# paperclick_v1.net
KiCad netlist of a schematic drawn in EAGLE
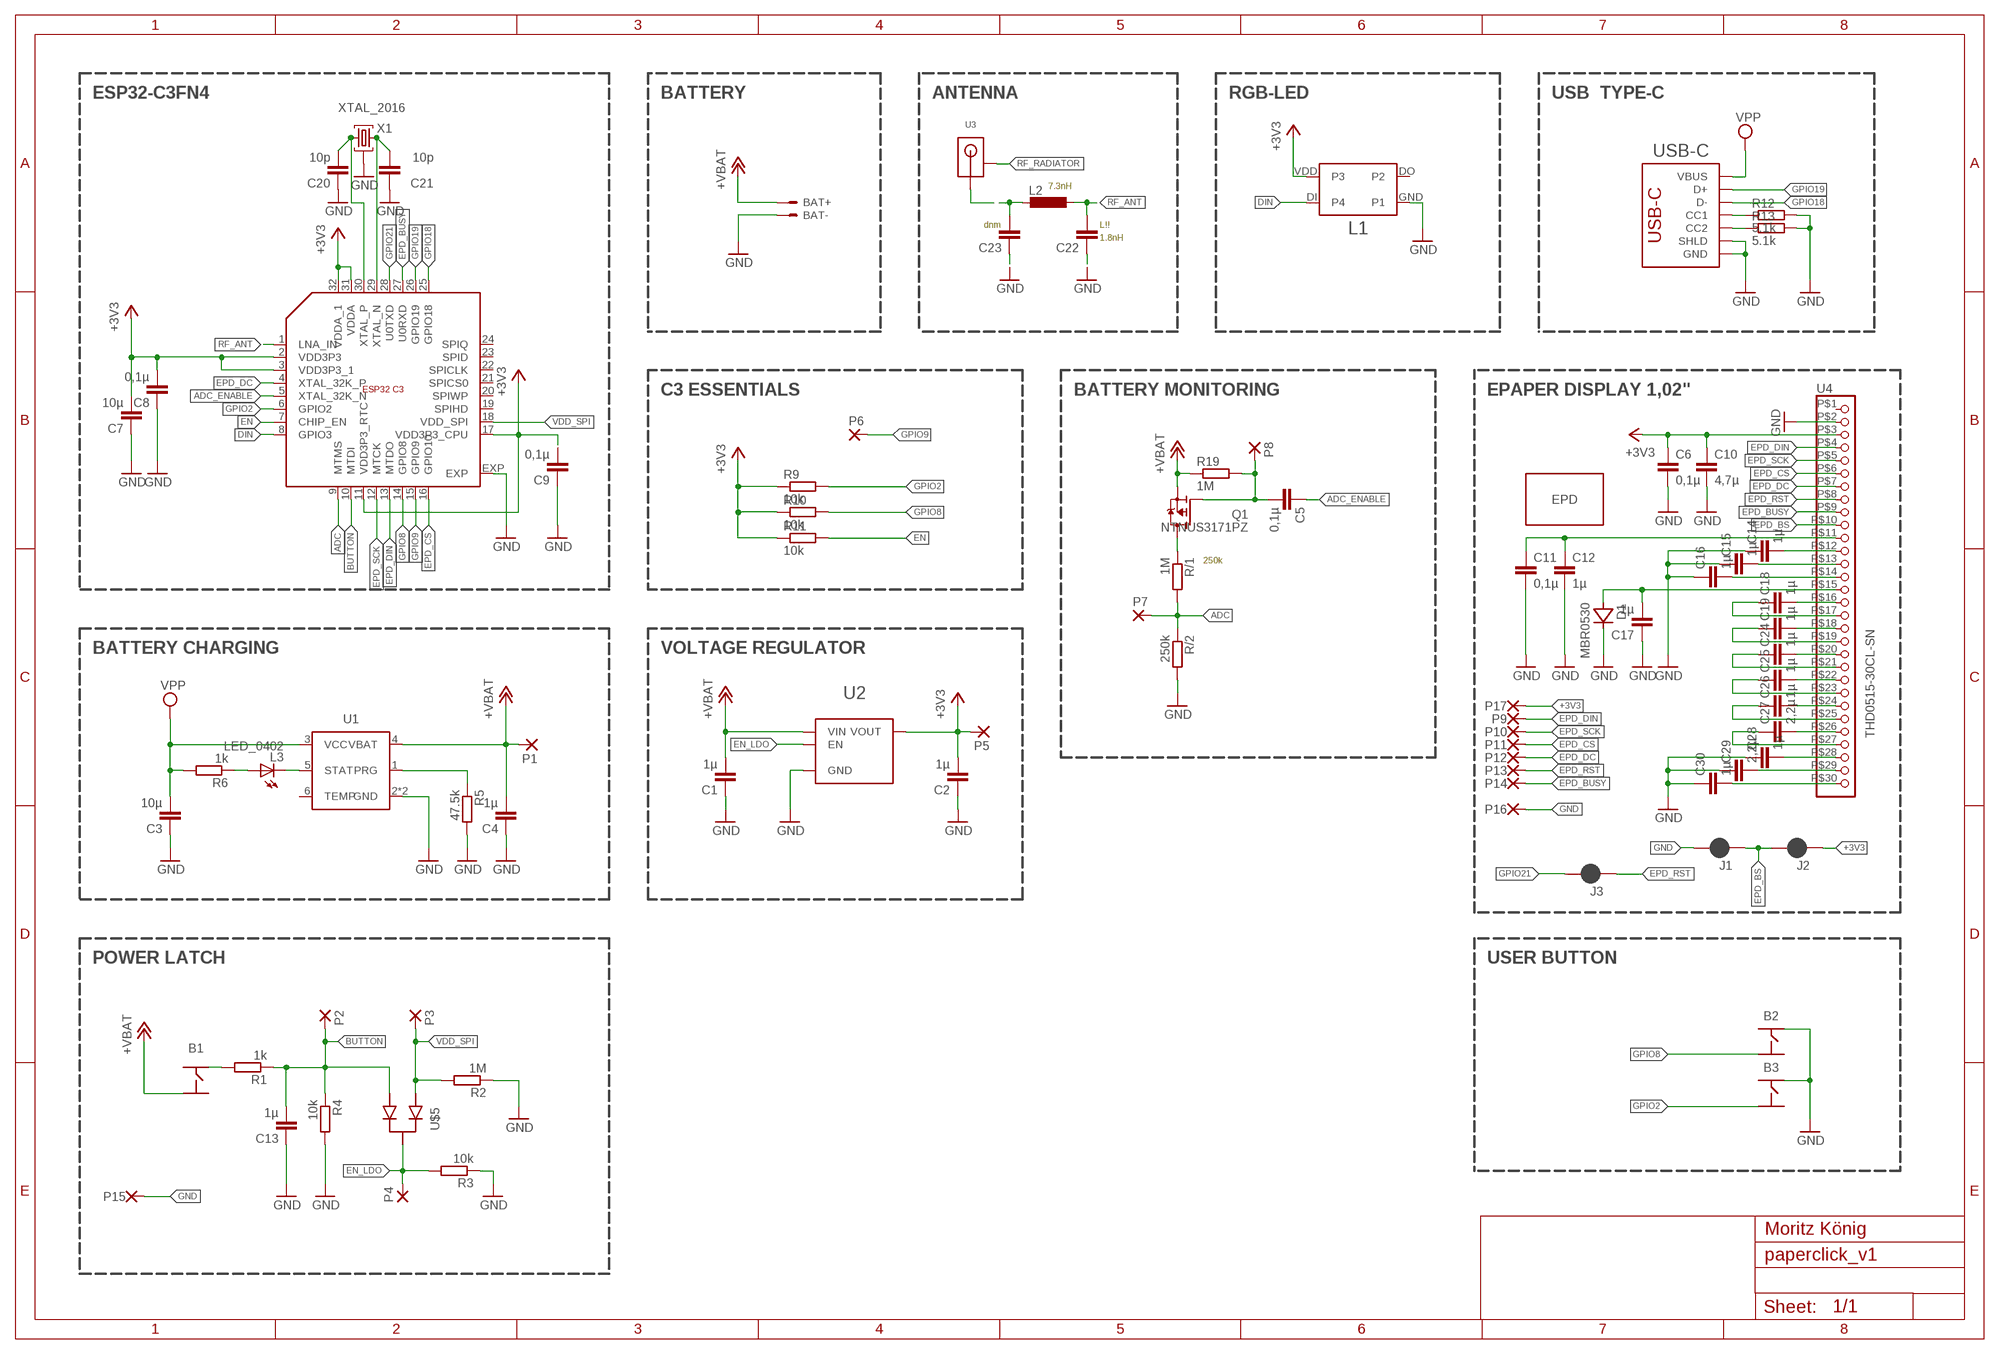
[diagram p0: schematic, sheet 1]

(export (version "E")
  (design (tool "Eeschema 10.0.6"))
  (components
    (comp (ref "B1")
      (value "BUTTON_4PIN_TS-1070A")
      (footprint "eagle-import:BUTTON_WHITE_SMD")
      (libsource (lib "eagle-import") (part "BUTTON_4PIN_TS-1070A"))
    )
    (comp (ref "B2")
      (value "PTS840ESDGMSMTRLFS")
      (footprint "eagle-import:PTS840ESDGMSMTRLFS")
      (libsource (lib "eagle-import") (part "PTS840ESDGMSMTRLFS"))
    )
    (comp (ref "B3")
      (value "PTS840ESDGMSMTRLFS")
      (footprint "eagle-import:PTS840ESDGMSMTRLFS")
      (libsource (lib "eagle-import") (part "PTS840ESDGMSMTRLFS"))
    )
    (comp (ref "BAT+")
      (value "TP/SP-1.5X1.0")
      (footprint "eagle-import:SOLDERPAD_1.5X1.0")
      (libsource (lib "eagle-import") (part "TP/SP-1.5X1.0"))
    )
    (comp (ref "BAT-")
      (value "TP/SP-1.5X1.0")
      (footprint "eagle-import:SOLDERPAD_1.5X1.0")
      (libsource (lib "eagle-import") (part "TP/SP-1.5X1.0"))
    )
    (comp (ref "C1")
      (value "1µ")
      (footprint "eagle-import:C0402_S")
      (libsource (lib "eagle-import") (part "C0402_S"))
    )
    (comp (ref "C2")
      (value "1µ")
      (footprint "eagle-import:C0402_S")
      (libsource (lib "eagle-import") (part "C0402_S"))
    )
    (comp (ref "C3")
      (value "10µ")
      (footprint "eagle-import:C0402_S")
      (libsource (lib "eagle-import") (part "C0402_S"))
    )
    (comp (ref "C4")
      (value "1µ")
      (footprint "eagle-import:C0402_S")
      (libsource (lib "eagle-import") (part "C0402_S"))
    )
    (comp (ref "C5")
      (value "0,1µ")
      (footprint "eagle-import:C0402_S")
      (libsource (lib "eagle-import") (part "C0402_S"))
    )
    (comp (ref "C6")
      (value "0,1µ")
      (footprint "eagle-import:C0402_S")
      (libsource (lib "eagle-import") (part "C0402_S"))
    )
    (comp (ref "C7")
      (value "10µ")
      (footprint "eagle-import:C0402_S")
      (libsource (lib "eagle-import") (part "C0402_S"))
    )
    (comp (ref "C8")
      (value "0,1µ")
      (footprint "eagle-import:C0402_S")
      (libsource (lib "eagle-import") (part "C0402_S"))
    )
    (comp (ref "C9")
      (value "0,1µ")
      (footprint "eagle-import:C0402_S")
      (libsource (lib "eagle-import") (part "C0402_S"))
    )
    (comp (ref "C10")
      (value "4,7µ")
      (footprint "eagle-import:C0402_S")
      (libsource (lib "eagle-import") (part "C0402_S"))
    )
    (comp (ref "C11")
      (value "0,1µ")
      (footprint "eagle-import:C0402_S")
      (libsource (lib "eagle-import") (part "C0402_S"))
    )
    (comp (ref "C12")
      (value "1µ")
      (footprint "eagle-import:C0402_S")
      (libsource (lib "eagle-import") (part "C0402_S"))
    )
    (comp (ref "C13")
      (value "1µ")
      (footprint "eagle-import:C0402_S")
      (libsource (lib "eagle-import") (part "C0402_S"))
    )
    (comp (ref "C14")
      (value "1µ")
      (footprint "eagle-import:C0402_S")
      (libsource (lib "eagle-import") (part "C0402_S"))
    )
    (comp (ref "C15")
      (value "1µ")
      (footprint "eagle-import:C0402_S")
      (libsource (lib "eagle-import") (part "C0402_S"))
    )
    (comp (ref "C16")
      (value "1µ")
      (footprint "eagle-import:C0402_S")
      (libsource (lib "eagle-import") (part "C0402_S"))
    )
    (comp (ref "C17")
      (value "1µ")
      (footprint "eagle-import:C0402_S")
      (libsource (lib "eagle-import") (part "C0402_S"))
    )
    (comp (ref "C18")
      (value "1µ")
      (footprint "eagle-import:C0402_S")
      (libsource (lib "eagle-import") (part "C0402_S"))
    )
    (comp (ref "C19")
      (value "1µ")
      (footprint "eagle-import:C0402_S")
      (libsource (lib "eagle-import") (part "C0402_S"))
    )
    (comp (ref "C20")
      (value "10p")
      (footprint "eagle-import:C0402_S")
      (libsource (lib "eagle-import") (part "C0402_S"))
    )
    (comp (ref "C21")
      (value "10p")
      (footprint "eagle-import:C0402_S")
      (libsource (lib "eagle-import") (part "C0402_S"))
    )
    (comp (ref "C22")
      (value "C0201")
      (footprint "eagle-import:C0201")
      (libsource (lib "eagle-import") (part "C0201"))
    )
    (comp (ref "C23")
      (value "C0201")
      (footprint "eagle-import:C0201")
      (libsource (lib "eagle-import") (part "C0201"))
    )
    (comp (ref "C24")
      (value "1µ")
      (footprint "eagle-import:C0402_S")
      (libsource (lib "eagle-import") (part "C0402_S"))
    )
    (comp (ref "C25")
      (value "1µ")
      (footprint "eagle-import:C0402_S")
      (libsource (lib "eagle-import") (part "C0402_S"))
    )
    (comp (ref "C26")
      (value "1µ")
      (footprint "eagle-import:C0402_S")
      (libsource (lib "eagle-import") (part "C0402_S"))
    )
    (comp (ref "C27")
      (value "2,2µ")
      (footprint "eagle-import:C0402_S")
      (libsource (lib "eagle-import") (part "C0402_S"))
    )
    (comp (ref "C28")
      (value "1µ")
      (footprint "eagle-import:C0402_S")
      (libsource (lib "eagle-import") (part "C0402_S"))
    )
    (comp (ref "C29")
      (value "2,2µ")
      (footprint "eagle-import:C0402_S")
      (libsource (lib "eagle-import") (part "C0402_S"))
    )
    (comp (ref "C30")
      (value "1µ")
      (footprint "eagle-import:C0402_S")
      (libsource (lib "eagle-import") (part "C0402_S"))
    )
    (comp (ref "D1")
      (value "MBR0530")
      (footprint "eagle-import:SOD123")
      (libsource (lib "eagle-import") (part "MBR0520"))
    )
    (comp (ref "ESP1")
      (value "ESP32_C3_QFN32")
      (footprint "eagle-import:QFN32")
      (libsource (lib "eagle-import") (part "ESP32_C3_QFN32"))
    )
    (comp (ref "J1")
      (value "SMT_JUMPER_2_NC_PASTE")
      (footprint "eagle-import:JUMPER_SMALL")
      (libsource (lib "eagle-import") (part "SMT_JUMPER_2_NC_PASTE"))
    )
    (comp (ref "J2")
      (value "SMT_JUMPER_2_NC_PASTE")
      (footprint "eagle-import:JUMPER_SMALL")
      (libsource (lib "eagle-import") (part "SMT_JUMPER_2_NC_PASTE"))
    )
    (comp (ref "J3")
      (value "SMT_JUMPER_2_NC_PASTE")
      (footprint "eagle-import:JUMPER_SMALL")
      (libsource (lib "eagle-import") (part "SMT_JUMPER_2_NC_PASTE"))
    )
    (comp (ref "L1")
      (value "WS2812_2020")
      (footprint "eagle-import:WS2812_2020")
      (libsource (lib "eagle-import") (part "WS2812_2020"))
    )
    (comp (ref "L2")
      (value "L0201")
      (footprint "eagle-import:L0201")
      (libsource (lib "eagle-import") (part "L0201"))
    )
    (comp (ref "L3")
      (value "LED_0402")
      (footprint "eagle-import:CHIPLED_0402")
      (libsource (lib "eagle-import") (part "LED_0402"))
    )
    (comp (ref "P1")
      (value "SMD-R1")
      (footprint "eagle-import:SMD-R1")
      (libsource (lib "eagle-import") (part "SMD-R1"))
    )
    (comp (ref "P2")
      (value "SMD-R1")
      (footprint "eagle-import:SMD-R1")
      (libsource (lib "eagle-import") (part "SMD-R1"))
    )
    (comp (ref "P3")
      (value "SMD-R1")
      (footprint "eagle-import:SMD-R1")
      (libsource (lib "eagle-import") (part "SMD-R1"))
    )
    (comp (ref "P4")
      (value "SMD-R1")
      (footprint "eagle-import:SMD-R1")
      (libsource (lib "eagle-import") (part "SMD-R1"))
    )
    (comp (ref "P5")
      (value "SMD-R1")
      (footprint "eagle-import:SMD-R1")
      (libsource (lib "eagle-import") (part "SMD-R1"))
    )
    (comp (ref "P6")
      (value "SMD-R1")
      (footprint "eagle-import:SMD-R1")
      (libsource (lib "eagle-import") (part "SMD-R1"))
    )
    (comp (ref "P7")
      (value "SMD-R1")
      (footprint "eagle-import:SMD-R1")
      (libsource (lib "eagle-import") (part "SMD-R1"))
    )
    (comp (ref "P8")
      (value "SMD-R1")
      (footprint "eagle-import:SMD-R1")
      (libsource (lib "eagle-import") (part "SMD-R1"))
    )
    (comp (ref "P9")
      (value "SMD-R1")
      (footprint "eagle-import:SMD-R1")
      (libsource (lib "eagle-import") (part "SMD-R1"))
    )
    (comp (ref "P10")
      (value "SMD-R1")
      (footprint "eagle-import:SMD-R1")
      (libsource (lib "eagle-import") (part "SMD-R1"))
    )
    (comp (ref "P11")
      (value "SMD-R1")
      (footprint "eagle-import:SMD-R1")
      (libsource (lib "eagle-import") (part "SMD-R1"))
    )
    (comp (ref "P12")
      (value "SMD-R1")
      (footprint "eagle-import:SMD-R1")
      (libsource (lib "eagle-import") (part "SMD-R1"))
    )
    (comp (ref "P13")
      (value "SMD-R1")
      (footprint "eagle-import:SMD-R1")
      (libsource (lib "eagle-import") (part "SMD-R1"))
    )
    (comp (ref "P14")
      (value "SMD-R1")
      (footprint "eagle-import:SMD-R1")
      (libsource (lib "eagle-import") (part "SMD-R1"))
    )
    (comp (ref "P15")
      (value "SMD-R1")
      (footprint "eagle-import:SMD-R1")
      (libsource (lib "eagle-import") (part "SMD-R1"))
    )
    (comp (ref "P16")
      (value "SMD-R1")
      (footprint "eagle-import:SMD-R1")
      (libsource (lib "eagle-import") (part "SMD-R1"))
    )
    (comp (ref "P17")
      (value "SMD-R1")
      (footprint "eagle-import:SMD-R1")
      (libsource (lib "eagle-import") (part "SMD-R1"))
    )
    (comp (ref "Q1")
      (value "NTNUS3171PZ")
      (footprint "eagle-import:SOT1123")
      (libsource (lib "eagle-import") (part "NTNUS3171PZ"))
    )
    (comp (ref "R/1")
      (value "1M")
      (footprint "eagle-import:R0402")
      (libsource (lib "eagle-import") (part "R0402"))
    )
    (comp (ref "R/2")
      (value "250k")
      (footprint "eagle-import:R0402")
      (libsource (lib "eagle-import") (part "R0402"))
    )
    (comp (ref "R1")
      (value "1k")
      (footprint "eagle-import:R0402")
      (libsource (lib "eagle-import") (part "R0402"))
    )
    (comp (ref "R2")
      (value "1M")
      (footprint "eagle-import:R0402")
      (libsource (lib "eagle-import") (part "R0402"))
    )
    (comp (ref "R3")
      (value "10k")
      (footprint "eagle-import:R0402")
      (libsource (lib "eagle-import") (part "R0402"))
    )
    (comp (ref "R4")
      (value "10k")
      (footprint "eagle-import:R0402")
      (libsource (lib "eagle-import") (part "R0402"))
    )
    (comp (ref "R5")
      (value "47.5k")
      (footprint "eagle-import:R0402")
      (libsource (lib "eagle-import") (part "R0402"))
    )
    (comp (ref "R6")
      (value "1k")
      (footprint "eagle-import:R0402")
      (libsource (lib "eagle-import") (part "R0402"))
    )
    (comp (ref "R9")
      (value "10k")
      (footprint "eagle-import:R0402")
      (libsource (lib "eagle-import") (part "R0402"))
    )
    (comp (ref "R10")
      (value "10k")
      (footprint "eagle-import:R0402")
      (libsource (lib "eagle-import") (part "R0402"))
    )
    (comp (ref "R11")
      (value "10k")
      (footprint "eagle-import:R0402")
      (libsource (lib "eagle-import") (part "R0402"))
    )
    (comp (ref "R12")
      (value "5.1k")
      (footprint "eagle-import:R0402")
      (libsource (lib "eagle-import") (part "R0402"))
    )
    (comp (ref "R13")
      (value "5.1k")
      (footprint "eagle-import:R0402")
      (libsource (lib "eagle-import") (part "R0402"))
    )
    (comp (ref "R19")
      (value "1M")
      (footprint "eagle-import:R0402")
      (libsource (lib "eagle-import") (part "R0402"))
    )
    (comp (ref "U$2")
      (value "EPD-102-30PIN-TW")
      (footprint "eagle-import:EPD-102-30PIN-TW")
      (libsource (lib "eagle-import") (part "EPD-102-30PIN-TW"))
    )
    (comp (ref "U$5")
      (value "DAN222")
      (footprint "eagle-import:SOT523")
      (libsource (lib "eagle-import") (part "DAN222"))
    )
    (comp (ref "U1")
      (value "WS4518D")
      (footprint "eagle-import:DFN-6")
      (libsource (lib "eagle-import") (part "WS4518D"))
    )
    (comp (ref "U2")
      (value "MIC5504")
      (footprint "eagle-import:TDFN4")
      (libsource (lib "eagle-import") (part "MIC5504"))
    )
    (comp (ref "U3")
      (value "ANT016008LCS2442MA2")
      (footprint "eagle-import:ANT016008LCS2442MA2")
      (libsource (lib "eagle-import") (part "ANT016008LCS2442MA2"))
    )
    (comp (ref "U4")
      (value "THD0515-30CL-SN")
      (footprint "eagle-import:THD0515-30CL-SN")
      (libsource (lib "eagle-import") (part "THD0515-30CL-SN"))
    )
    (comp (ref "USB-C")
      (value "USB_C_C393939")
      (footprint "eagle-import:USBC_C393939")
      (libsource (lib "eagle-import") (part "USB_C_C393939"))
    )
    (comp (ref "X1")
      (value "XTAL_2016")
      (footprint "eagle-import:XTAL_2016")
      (libsource (lib "eagle-import") (part "XTAL_2016"))
    )
  )
  (nets
    (net (code "1") (name "+3V3") (class "Default")
      (node (ref "C10") (pin "P$1") (pinfunction "1_P$1") (pintype "passive"))
      (node (ref "C2") (pin "P$2") (pinfunction "2_P$2") (pintype "passive"))
      (node (ref "C6") (pin "P$1") (pinfunction "1_P$1") (pintype "passive"))
      (node (ref "C7") (pin "P$2") (pinfunction "2_P$2") (pintype "passive"))
      (node (ref "C8") (pin "P$2") (pinfunction "2_P$2") (pintype "passive"))
      (node (ref "C9") (pin "P$2") (pinfunction "2_P$2") (pintype "passive"))
      (node (ref "ESP1") (pin "11") (pinfunction "VDD3P3_RTC_11") (pintype "bidirectional"))
      (node (ref "ESP1") (pin "17") (pinfunction "VDD3P3_CPU_17") (pintype "bidirectional"))
      (node (ref "ESP1") (pin "2") (pinfunction "VDD3P3_2") (pintype "bidirectional"))
      (node (ref "ESP1") (pin "3") (pinfunction "VDD3P3_1_3") (pintype "bidirectional"))
      (node (ref "ESP1") (pin "31") (pinfunction "VDDA_31") (pintype "bidirectional"))
      (node (ref "ESP1") (pin "32") (pinfunction "VDDA_1_32") (pintype "bidirectional"))
      (node (ref "J2") (pin "P$1") (pinfunction "1_P$1") (pintype "passive"))
      (node (ref "L1") (pin "VDD") (pinfunction "P3_VDD") (pintype "bidirectional"))
      (node (ref "P17") (pin "P$1") (pinfunction "P_P$1") (pintype "passive"))
      (node (ref "P5") (pin "P$1") (pinfunction "P_P$1") (pintype "passive"))
      (node (ref "R10") (pin "1") (pinfunction "1_1") (pintype "passive"))
      (node (ref "R11") (pin "1") (pinfunction "1_1") (pintype "passive"))
      (node (ref "R9") (pin "1") (pinfunction "1_1") (pintype "passive"))
      (node (ref "U2") (pin "P1") (pinfunction "VOUT_P1") (pintype "bidirectional"))
      (node (ref "U4") (pin "P$3") (pinfunction "3_P$3") (pintype "passive"))
    )
    (net (code "2") (name "+VBAT") (class "Default")
      (node (ref "B1") (pin "P$2") (pinfunction "3_P$2") (pintype "bidirectional"))
      (node (ref "BAT+") (pin "1") (pinfunction "S_1") (pintype "passive"))
      (node (ref "C1") (pin "P$2") (pinfunction "2_P$2") (pintype "passive"))
      (node (ref "C4") (pin "P$2") (pinfunction "2_P$2") (pintype "passive"))
      (node (ref "P1") (pin "P$1") (pinfunction "P_P$1") (pintype "passive"))
      (node (ref "Q1") (pin "2") (pinfunction "S_2") (pintype "passive"))
      (node (ref "R19") (pin "1") (pinfunction "1_1") (pintype "passive"))
      (node (ref "U1") (pin "4") (pinfunction "VBAT_4") (pintype "bidirectional"))
      (node (ref "U2") (pin "P4") (pinfunction "VIN_P4") (pintype "bidirectional"))
    )
    (net (code "3") (name "ADC") (class "Default")
      (node (ref "ESP1") (pin "9") (pinfunction "MTMS_9") (pintype "bidirectional"))
      (node (ref "P7") (pin "P$1") (pinfunction "P_P$1") (pintype "passive"))
      (node (ref "R/1") (pin "2") (pinfunction "2_2") (pintype "passive"))
      (node (ref "R/2") (pin "1") (pinfunction "1_1") (pintype "passive"))
    )
    (net (code "4") (name "ADC_ENABLE") (class "Default")
      (node (ref "C5") (pin "P$1") (pinfunction "1_P$1") (pintype "passive"))
      (node (ref "ESP1") (pin "5") (pinfunction "XTAL_32K_N_5") (pintype "bidirectional"))
    )
    (net (code "5") (name "BUTTON") (class "Default")
      (node (ref "C13") (pin "P$2") (pinfunction "2_P$2") (pintype "passive"))
      (node (ref "ESP1") (pin "10") (pinfunction "MTDI_10") (pintype "bidirectional"))
      (node (ref "P2") (pin "P$1") (pinfunction "P_P$1") (pintype "passive"))
      (node (ref "R1") (pin "1") (pinfunction "1_1") (pintype "passive"))
      (node (ref "R4") (pin "1") (pinfunction "1_1") (pintype "passive"))
      (node (ref "U$5") (pin "2") (pinfunction "2_2") (pintype "bidirectional"))
    )
    (net (code "6") (name "DIN") (class "Default")
      (node (ref "ESP1") (pin "8") (pinfunction "GPIO3_8") (pintype "bidirectional"))
      (node (ref "L1") (pin "DI") (pinfunction "P4_DI") (pintype "bidirectional"))
    )
    (net (code "7") (name "EN") (class "Default")
      (node (ref "ESP1") (pin "7") (pinfunction "CHIP_EN_7") (pintype "bidirectional"))
      (node (ref "R11") (pin "2") (pinfunction "2_2") (pintype "passive"))
    )
    (net (code "8") (name "EN_LDO") (class "Default")
      (node (ref "P4") (pin "P$1") (pinfunction "P_P$1") (pintype "passive"))
      (node (ref "R3") (pin "2") (pinfunction "2_2") (pintype "passive"))
      (node (ref "U$5") (pin "3") (pinfunction "3_3") (pintype "bidirectional"))
      (node (ref "U2") (pin "P3") (pinfunction "EN_P3") (pintype "bidirectional"))
    )
    (net (code "9") (name "EPD_BS") (class "Default")
      (node (ref "J1") (pin "P$1") (pinfunction "1_P$1") (pintype "passive"))
      (node (ref "J2") (pin "P$2") (pinfunction "2_P$2") (pintype "passive"))
      (node (ref "U4") (pin "P$10") (pinfunction "10_P$10") (pintype "passive"))
    )
    (net (code "10") (name "EPD_BUSY") (class "Default")
      (node (ref "ESP1") (pin "27") (pinfunction "U0RXD_27") (pintype "bidirectional"))
      (node (ref "P14") (pin "P$1") (pinfunction "P_P$1") (pintype "passive"))
      (node (ref "U4") (pin "P$9") (pinfunction "9_P$9") (pintype "passive"))
    )
    (net (code "11") (name "EPD_CS") (class "Default")
      (node (ref "ESP1") (pin "16") (pinfunction "GPIO10_16") (pintype "bidirectional"))
      (node (ref "P11") (pin "P$1") (pinfunction "P_P$1") (pintype "passive"))
      (node (ref "U4") (pin "P$6") (pinfunction "6_P$6") (pintype "passive"))
    )
    (net (code "12") (name "EPD_DC") (class "Default")
      (node (ref "ESP1") (pin "4") (pinfunction "XTAL_32K_P_4") (pintype "bidirectional"))
      (node (ref "P12") (pin "P$1") (pinfunction "P_P$1") (pintype "passive"))
      (node (ref "U4") (pin "P$7") (pinfunction "7_P$7") (pintype "passive"))
    )
    (net (code "13") (name "EPD_DIN") (class "Default")
      (node (ref "ESP1") (pin "13") (pinfunction "MTDO_13") (pintype "bidirectional"))
      (node (ref "P9") (pin "P$1") (pinfunction "P_P$1") (pintype "passive"))
      (node (ref "U4") (pin "P$4") (pinfunction "4_P$4") (pintype "passive"))
    )
    (net (code "14") (name "EPD_RST") (class "Default")
      (node (ref "J3") (pin "P$1") (pinfunction "1_P$1") (pintype "passive"))
      (node (ref "P13") (pin "P$1") (pinfunction "P_P$1") (pintype "passive"))
      (node (ref "U4") (pin "P$8") (pinfunction "8_P$8") (pintype "passive"))
    )
    (net (code "15") (name "EPD_SCK") (class "Default")
      (node (ref "ESP1") (pin "12") (pinfunction "MTCK_12") (pintype "bidirectional"))
      (node (ref "P10") (pin "P$1") (pinfunction "P_P$1") (pintype "passive"))
      (node (ref "U4") (pin "P$5") (pinfunction "5_P$5") (pintype "passive"))
    )
    (net (code "16") (name "GND") (class "Default")
      (node (ref "B2") (pin "2") (pinfunction "2_2") (pintype "bidirectional"))
      (node (ref "B3") (pin "2") (pinfunction "2_2") (pintype "bidirectional"))
      (node (ref "BAT-") (pin "1") (pinfunction "S_1") (pintype "passive"))
      (node (ref "C1") (pin "P$1") (pinfunction "1_P$1") (pintype "passive"))
      (node (ref "C10") (pin "P$2") (pinfunction "2_P$2") (pintype "passive"))
      (node (ref "C11") (pin "P$2") (pinfunction "2_P$2") (pintype "passive"))
      (node (ref "C12") (pin "P$2") (pinfunction "2_P$2") (pintype "passive"))
      (node (ref "C13") (pin "P$1") (pinfunction "1_P$1") (pintype "passive"))
      (node (ref "C14") (pin "P$1") (pinfunction "1_P$1") (pintype "passive"))
      (node (ref "C15") (pin "P$1") (pinfunction "1_P$1") (pintype "passive"))
      (node (ref "C16") (pin "P$1") (pinfunction "1_P$1") (pintype "passive"))
      (node (ref "C17") (pin "P$1") (pinfunction "1_P$1") (pintype "passive"))
      (node (ref "C2") (pin "P$1") (pinfunction "1_P$1") (pintype "passive"))
      (node (ref "C20") (pin "P$1") (pinfunction "1_P$1") (pintype "passive"))
      (node (ref "C21") (pin "P$1") (pinfunction "1_P$1") (pintype "passive"))
      (node (ref "C22") (pin "P$1") (pinfunction "1_P$1") (pintype "passive"))
      (node (ref "C23") (pin "P$1") (pinfunction "1_P$1") (pintype "passive"))
      (node (ref "C28") (pin "P$1") (pinfunction "1_P$1") (pintype "passive"))
      (node (ref "C29") (pin "P$1") (pinfunction "1_P$1") (pintype "passive"))
      (node (ref "C3") (pin "P$1") (pinfunction "1_P$1") (pintype "passive"))
      (node (ref "C30") (pin "P$1") (pinfunction "1_P$1") (pintype "passive"))
      (node (ref "C4") (pin "P$1") (pinfunction "1_P$1") (pintype "passive"))
      (node (ref "C6") (pin "P$2") (pinfunction "2_P$2") (pintype "passive"))
      (node (ref "C7") (pin "P$1") (pinfunction "1_P$1") (pintype "passive"))
      (node (ref "C8") (pin "P$1") (pinfunction "1_P$1") (pintype "passive"))
      (node (ref "C9") (pin "P$1") (pinfunction "1_P$1") (pintype "passive"))
      (node (ref "D1") (pin "P$2") (pinfunction "C_P$2") (pintype "passive"))
      (node (ref "ESP1") (pin "EXP") (pinfunction "EXP_EXP") (pintype "bidirectional"))
      (node (ref "J1") (pin "P$2") (pinfunction "2_P$2") (pintype "passive"))
      (node (ref "L1") (pin "GND") (pinfunction "P1_GND") (pintype "bidirectional"))
      (node (ref "P15") (pin "P$1") (pinfunction "P_P$1") (pintype "passive"))
      (node (ref "P16") (pin "P$1") (pinfunction "P_P$1") (pintype "passive"))
      (node (ref "R/2") (pin "2") (pinfunction "2_2") (pintype "passive"))
      (node (ref "R12") (pin "2") (pinfunction "2_2") (pintype "passive"))
      (node (ref "R13") (pin "2") (pinfunction "2_2") (pintype "passive"))
      (node (ref "R2") (pin "1") (pinfunction "1_1") (pintype "passive"))
      (node (ref "R3") (pin "1") (pinfunction "1_1") (pintype "passive"))
      (node (ref "R4") (pin "2") (pinfunction "2_2") (pintype "passive"))
      (node (ref "R5") (pin "2") (pinfunction "2_2") (pintype "passive"))
      (node (ref "U1") (pin "2") (pinfunction "GND_2") (pintype "bidirectional"))
      (node (ref "U1") (pin "EXP") (pinfunction "GND_EXP") (pintype "bidirectional"))
      (node (ref "U2") (pin "EXP") (pinfunction "GND_EXP") (pintype "bidirectional"))
      (node (ref "U2") (pin "P2") (pinfunction "GND_P2") (pintype "bidirectional"))
      (node (ref "U4") (pin "P$2") (pinfunction "2_P$2") (pintype "passive"))
      (node (ref "USB-C") (pin "A1B12") (pinfunction "GND_A1B12") (pintype "bidirectional"))
      (node (ref "USB-C") (pin "B1A12") (pinfunction "GND_B1A12") (pintype "bidirectional"))
      (node (ref "USB-C") (pin "S1") (pinfunction "SHLD_S1") (pintype "bidirectional"))
      (node (ref "USB-C") (pin "S2") (pinfunction "SHLD_S2") (pintype "bidirectional"))
      (node (ref "USB-C") (pin "S3") (pinfunction "SHLD_S3") (pintype "bidirectional"))
      (node (ref "USB-C") (pin "S4") (pinfunction "SHLD_S4") (pintype "bidirectional"))
      (node (ref "X1") (pin "P2") (pinfunction "G_P2") (pintype "passive"))
      (node (ref "X1") (pin "P4") (pinfunction "G_P4") (pintype "passive"))
    )
    (net (code "17") (name "GPIO2") (class "Default")
      (node (ref "B3") (pin "3") (pinfunction "3_3") (pintype "bidirectional"))
      (node (ref "ESP1") (pin "6") (pinfunction "GPIO2_6") (pintype "bidirectional"))
      (node (ref "R9") (pin "2") (pinfunction "2_2") (pintype "passive"))
    )
    (net (code "18") (name "GPIO8") (class "Default")
      (node (ref "B2") (pin "3") (pinfunction "3_3") (pintype "bidirectional"))
      (node (ref "ESP1") (pin "14") (pinfunction "GPIO8_14") (pintype "bidirectional"))
      (node (ref "R10") (pin "2") (pinfunction "2_2") (pintype "passive"))
    )
    (net (code "19") (name "GPIO9") (class "Default")
      (node (ref "ESP1") (pin "15") (pinfunction "GPIO9_15") (pintype "bidirectional"))
      (node (ref "P6") (pin "P$1") (pinfunction "P_P$1") (pintype "passive"))
    )
    (net (code "20") (name "GPIO18") (class "Default")
      (node (ref "ESP1") (pin "25") (pinfunction "GPIO18_25") (pintype "bidirectional"))
      (node (ref "USB-C") (pin "A7") (pinfunction "D-_A7") (pintype "bidirectional"))
      (node (ref "USB-C") (pin "B7") (pinfunction "D-_B7") (pintype "bidirectional"))
    )
    (net (code "21") (name "GPIO19") (class "Default")
      (node (ref "ESP1") (pin "26") (pinfunction "GPIO19_26") (pintype "bidirectional"))
      (node (ref "USB-C") (pin "A6") (pinfunction "D+_A6") (pintype "bidirectional"))
      (node (ref "USB-C") (pin "B6") (pinfunction "D+_B6") (pintype "bidirectional"))
    )
    (net (code "22") (name "GPIO21") (class "Default")
      (node (ref "ESP1") (pin "28") (pinfunction "U0TXD_28") (pintype "bidirectional"))
      (node (ref "J3") (pin "P$2") (pinfunction "2_P$2") (pintype "passive"))
    )
    (net (code "23") (name "Net-(B1-2)") (class "Default")
      (node (ref "B1") (pin "P$4") (pinfunction "2_P$4") (pintype "bidirectional"))
      (node (ref "R1") (pin "2") (pinfunction "2_2") (pintype "passive"))
    )
    (net (code "24") (name "Net-(C5-2)") (class "Default")
      (node (ref "C5") (pin "P$2") (pinfunction "2_P$2") (pintype "passive"))
      (node (ref "P8") (pin "P$1") (pinfunction "P_P$1") (pintype "passive"))
      (node (ref "Q1") (pin "1") (pinfunction "G_1") (pintype "passive"))
      (node (ref "R19") (pin "2") (pinfunction "2_2") (pintype "passive"))
    )
    (net (code "25") (name "Net-(C11-1)") (class "Default")
      (node (ref "C11") (pin "P$1") (pinfunction "1_P$1") (pintype "passive"))
      (node (ref "C12") (pin "P$1") (pinfunction "1_P$1") (pintype "passive"))
      (node (ref "U4") (pin "P$11") (pinfunction "11_P$11") (pintype "passive"))
    )
    (net (code "26") (name "Net-(C14-2)") (class "Default")
      (node (ref "C14") (pin "P$2") (pinfunction "2_P$2") (pintype "passive"))
      (node (ref "U4") (pin "P$12") (pinfunction "12_P$12") (pintype "passive"))
    )
    (net (code "27") (name "Net-(C15-2)") (class "Default")
      (node (ref "C15") (pin "P$2") (pinfunction "2_P$2") (pintype "passive"))
      (node (ref "U4") (pin "P$13") (pinfunction "13_P$13") (pintype "passive"))
    )
    (net (code "28") (name "Net-(C16-2)") (class "Default")
      (node (ref "C16") (pin "P$2") (pinfunction "2_P$2") (pintype "passive"))
      (node (ref "U4") (pin "P$14") (pinfunction "14_P$14") (pintype "passive"))
    )
    (net (code "29") (name "Net-(C17-2)") (class "Default")
      (node (ref "C17") (pin "P$2") (pinfunction "2_P$2") (pintype "passive"))
      (node (ref "D1") (pin "P$1") (pinfunction "A_P$1") (pintype "passive"))
      (node (ref "U4") (pin "P$15") (pinfunction "15_P$15") (pintype "passive"))
    )
    (net (code "30") (name "Net-(C18-1)") (class "Default")
      (node (ref "C18") (pin "P$1") (pinfunction "1_P$1") (pintype "passive"))
      (node (ref "U4") (pin "P$17") (pinfunction "17_P$17") (pintype "passive"))
    )
    (net (code "31") (name "Net-(C18-2)") (class "Default")
      (node (ref "C18") (pin "P$2") (pinfunction "2_P$2") (pintype "passive"))
      (node (ref "U4") (pin "P$16") (pinfunction "16_P$16") (pintype "passive"))
    )
    (net (code "32") (name "Net-(C19-1)") (class "Default")
      (node (ref "C19") (pin "P$1") (pinfunction "1_P$1") (pintype "passive"))
      (node (ref "U4") (pin "P$19") (pinfunction "19_P$19") (pintype "passive"))
    )
    (net (code "33") (name "Net-(C19-2)") (class "Default")
      (node (ref "C19") (pin "P$2") (pinfunction "2_P$2") (pintype "passive"))
      (node (ref "U4") (pin "P$18") (pinfunction "18_P$18") (pintype "passive"))
    )
    (net (code "34") (name "Net-(C20-2)") (class "Default")
      (node (ref "C20") (pin "P$2") (pinfunction "2_P$2") (pintype "passive"))
      (node (ref "ESP1") (pin "30") (pinfunction "XTAL_P_30") (pintype "bidirectional"))
      (node (ref "X1") (pin "P1") (pinfunction "1_P1") (pintype "passive"))
    )
    (net (code "35") (name "Net-(C21-2)") (class "Default")
      (node (ref "C21") (pin "P$2") (pinfunction "2_P$2") (pintype "passive"))
      (node (ref "ESP1") (pin "29") (pinfunction "XTAL_N_29") (pintype "bidirectional"))
      (node (ref "X1") (pin "P3") (pinfunction "2_P3") (pintype "passive"))
    )
    (net (code "36") (name "Net-(C23-2)") (class "Default")
      (node (ref "C23") (pin "P$2") (pinfunction "2_P$2") (pintype "passive"))
      (node (ref "L2") (pin "P$2") (pinfunction "2_P$2") (pintype "passive"))
      (node (ref "U3") (pin "3") (pinfunction "ANT_3") (pintype "bidirectional"))
    )
    (net (code "37") (name "Net-(C24-1)") (class "Default")
      (node (ref "C24") (pin "P$1") (pinfunction "1_P$1") (pintype "passive"))
      (node (ref "U4") (pin "P$21") (pinfunction "21_P$21") (pintype "passive"))
    )
    (net (code "38") (name "Net-(C24-2)") (class "Default")
      (node (ref "C24") (pin "P$2") (pinfunction "2_P$2") (pintype "passive"))
      (node (ref "U4") (pin "P$20") (pinfunction "20_P$20") (pintype "passive"))
    )
    (net (code "39") (name "Net-(C25-1)") (class "Default")
      (node (ref "C25") (pin "P$1") (pinfunction "1_P$1") (pintype "passive"))
      (node (ref "U4") (pin "P$23") (pinfunction "23_P$23") (pintype "passive"))
    )
    (net (code "40") (name "Net-(C25-2)") (class "Default")
      (node (ref "C25") (pin "P$2") (pinfunction "2_P$2") (pintype "passive"))
      (node (ref "U4") (pin "P$22") (pinfunction "22_P$22") (pintype "passive"))
    )
    (net (code "41") (name "Net-(C26-1)") (class "Default")
      (node (ref "C26") (pin "P$1") (pinfunction "1_P$1") (pintype "passive"))
      (node (ref "U4") (pin "P$25") (pinfunction "25_P$25") (pintype "passive"))
    )
    (net (code "42") (name "Net-(C26-2)") (class "Default")
      (node (ref "C26") (pin "P$2") (pinfunction "2_P$2") (pintype "passive"))
      (node (ref "U4") (pin "P$24") (pinfunction "24_P$24") (pintype "passive"))
    )
    (net (code "43") (name "Net-(C27-1)") (class "Default")
      (node (ref "C27") (pin "P$1") (pinfunction "1_P$1") (pintype "passive"))
      (node (ref "U4") (pin "P$27") (pinfunction "27_P$27") (pintype "passive"))
    )
    (net (code "44") (name "Net-(C27-2)") (class "Default")
      (node (ref "C27") (pin "P$2") (pinfunction "2_P$2") (pintype "passive"))
      (node (ref "U4") (pin "P$26") (pinfunction "26_P$26") (pintype "passive"))
    )
    (net (code "45") (name "Net-(C28-2)") (class "Default")
      (node (ref "C28") (pin "P$2") (pinfunction "2_P$2") (pintype "passive"))
      (node (ref "U4") (pin "P$28") (pinfunction "28_P$28") (pintype "passive"))
    )
    (net (code "46") (name "Net-(C29-2)") (class "Default")
      (node (ref "C29") (pin "P$2") (pinfunction "2_P$2") (pintype "passive"))
      (node (ref "U4") (pin "P$29") (pinfunction "29_P$29") (pintype "passive"))
    )
    (net (code "47") (name "Net-(C30-2)") (class "Default")
      (node (ref "C30") (pin "P$2") (pinfunction "2_P$2") (pintype "passive"))
      (node (ref "U4") (pin "P$30") (pinfunction "30_P$30") (pintype "passive"))
    )
    (net (code "48") (name "Net-(L3-A)") (class "Default")
      (node (ref "L3") (pin "P$2") (pinfunction "A_P$2") (pintype "passive"))
      (node (ref "R6") (pin "1") (pinfunction "1_1") (pintype "passive"))
    )
    (net (code "49") (name "Net-(L3-C)") (class "Default")
      (node (ref "L3") (pin "P$1") (pinfunction "C_P$1") (pintype "passive"))
      (node (ref "U1") (pin "5") (pinfunction "STAT_5") (pintype "bidirectional"))
    )
    (net (code "50") (name "Net-(Q1-D)") (class "Default")
      (node (ref "Q1") (pin "3") (pinfunction "D_3") (pintype "passive"))
      (node (ref "R/1") (pin "1") (pinfunction "1_1") (pintype "passive"))
    )
    (net (code "51") (name "Net-(U1-PRG)") (class "Default")
      (node (ref "R5") (pin "1") (pinfunction "1_1") (pintype "passive"))
      (node (ref "U1") (pin "1") (pinfunction "PRG_1") (pintype "bidirectional"))
    )
    (net (code "52") (name "Net-(USB-C-CC1)") (class "Default")
      (node (ref "R12") (pin "1") (pinfunction "1_1") (pintype "passive"))
      (node (ref "USB-C") (pin "A5") (pinfunction "CC1_A5") (pintype "bidirectional"))
    )
    (net (code "53") (name "Net-(USB-C-CC2)") (class "Default")
      (node (ref "R13") (pin "1") (pinfunction "1_1") (pintype "passive"))
      (node (ref "USB-C") (pin "B5") (pinfunction "CC2_B5") (pintype "bidirectional"))
    )
    (net (code "54") (name "RF_ANT") (class "Default")
      (node (ref "C22") (pin "P$2") (pinfunction "2_P$2") (pintype "passive"))
      (node (ref "ESP1") (pin "1") (pinfunction "LNA_IN_1") (pintype "bidirectional"))
      (node (ref "L2") (pin "P$1") (pinfunction "1_P$1") (pintype "passive"))
    )
    (net (code "55") (name "RF_RADIATOR") (class "Default")
      (node (ref "U3") (pin "1") (pinfunction "GND_1") (pintype "bidirectional"))
    )
    (net (code "56") (name "VDD_SPI") (class "Default")
      (node (ref "ESP1") (pin "18") (pinfunction "VDD_SPI_18") (pintype "bidirectional"))
      (node (ref "P3") (pin "P$1") (pinfunction "P_P$1") (pintype "passive"))
      (node (ref "R2") (pin "2") (pinfunction "2_2") (pintype "passive"))
      (node (ref "U$5") (pin "1") (pinfunction "1_1") (pintype "bidirectional"))
    )
    (net (code "57") (name "VPP") (class "Default")
      (node (ref "C3") (pin "P$2") (pinfunction "2_P$2") (pintype "passive"))
      (node (ref "R6") (pin "2") (pinfunction "2_2") (pintype "passive"))
      (node (ref "U1") (pin "3") (pinfunction "VCC_3") (pintype "bidirectional"))
      (node (ref "USB-C") (pin "A4B9") (pinfunction "VBUS_A4B9") (pintype "bidirectional"))
      (node (ref "USB-C") (pin "B4A9") (pinfunction "VBUS_B4A9") (pintype "bidirectional"))
    )
    (net (code "58") (name "unconnected-(B1-1-PadP$1)") (class "Default")
      (node (ref "B1") (pin "P$1") (pinfunction "1_P$1") (pintype "bidirectional"))
    )
    (net (code "59") (name "unconnected-(B1-4-PadP$3)") (class "Default")
      (node (ref "B1") (pin "P$3") (pinfunction "4_P$3") (pintype "bidirectional"))
    )
    (net (code "60") (name "unconnected-(B2-Pad1)") (class "Default")
      (node (ref "B2") (pin "1") (pinfunction "1_1") (pintype "bidirectional"))
    )
    (net (code "61") (name "unconnected-(B2-Pad4)") (class "Default")
      (node (ref "B2") (pin "4") (pinfunction "4_4") (pintype "bidirectional"))
    )
    (net (code "62") (name "unconnected-(B2-Pad5)") (class "Default")
      (node (ref "B2") (pin "5") (pinfunction "5_5") (pintype "bidirectional"))
    )
    (net (code "63") (name "unconnected-(B3-Pad1)") (class "Default")
      (node (ref "B3") (pin "1") (pinfunction "1_1") (pintype "bidirectional"))
    )
    (net (code "64") (name "unconnected-(B3-Pad4)") (class "Default")
      (node (ref "B3") (pin "4") (pinfunction "4_4") (pintype "bidirectional"))
    )
    (net (code "65") (name "unconnected-(B3-Pad5)") (class "Default")
      (node (ref "B3") (pin "5") (pinfunction "5_5") (pintype "bidirectional"))
    )
    (net (code "66") (name "unconnected-(ESP1-SPICLK-Pad22)") (class "Default")
      (node (ref "ESP1") (pin "22") (pinfunction "SPICLK_22") (pintype "bidirectional"))
    )
    (net (code "67") (name "unconnected-(ESP1-SPICS0-Pad21)") (class "Default")
      (node (ref "ESP1") (pin "21") (pinfunction "SPICS0_21") (pintype "bidirectional"))
    )
    (net (code "68") (name "unconnected-(ESP1-SPID-Pad23)") (class "Default")
      (node (ref "ESP1") (pin "23") (pinfunction "SPID_23") (pintype "bidirectional"))
    )
    (net (code "69") (name "unconnected-(ESP1-SPIHD-Pad19)") (class "Default")
      (node (ref "ESP1") (pin "19") (pinfunction "SPIHD_19") (pintype "bidirectional"))
    )
    (net (code "70") (name "unconnected-(ESP1-SPIQ-Pad24)") (class "Default")
      (node (ref "ESP1") (pin "24") (pinfunction "SPIQ_24") (pintype "bidirectional"))
    )
    (net (code "71") (name "unconnected-(ESP1-SPIWP-Pad20)") (class "Default")
      (node (ref "ESP1") (pin "20") (pinfunction "SPIWP_20") (pintype "bidirectional"))
    )
    (net (code "72") (name "unconnected-(L1-P2-PadDO)") (class "Default")
      (node (ref "L1") (pin "DO") (pinfunction "P2_DO") (pintype "bidirectional"))
    )
    (net (code "73") (name "unconnected-(U1-TEMP-Pad6)") (class "Default")
      (node (ref "U1") (pin "6") (pinfunction "TEMP_6") (pintype "bidirectional"))
    )
    (net (code "74") (name "unconnected-(U4-1-PadP$1)") (class "Default")
      (node (ref "U4") (pin "P$1") (pinfunction "1_P$1") (pintype "passive"))
    )
  )
)
